# Power.net
KiCad netlist of a schematic drawn in Altium Designer
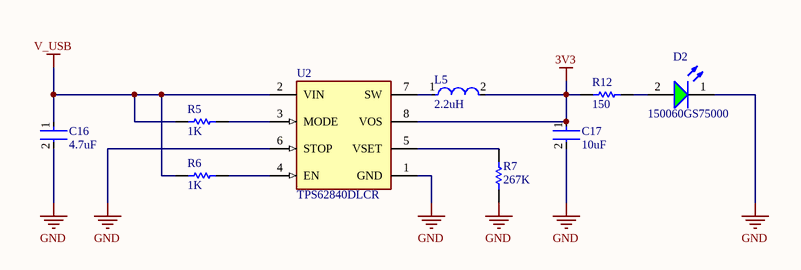
[diagram p0: Power.SchDoc]

(export (version "E")
  (design (tool "Eeschema 10.0.6"))
  (components
    (comp (ref "C16")
      (value "4.7uF")
      (footprint "FP-CC0402-MFG")
      (description "CAP CER 4.7UF 16V X5R 0402")
      (fields
        (field (name "OCTOPART") "https://octopart.com/cc0402mrx5r7bb475-yageo-81932628")
        (field (name "MANUFACTURER PART NUMBER") "CC0402MRX5R7BB475")
      )
      (libsource (lib "Altium Content Vault") (part "11868f565c42a9108669ba33697ecf6"))
    )
    (comp (ref "C17")
      (value "10uF")
      (footprint "FP-CL07-IPC_C")
      (description "Cap Ceramic 10uF 10V X5R ±20% SMD 0402 +85°C Paper T/R")
      (fields (field (name "TOLERANCE") "20%"))
      (libsource (lib "Altium Content Vault") (part "b4654b650e69147ec39a6b967a45e02"))
    )
    (comp (ref "D2")
      (value "150060GS75000")
      (footprint "WL-SMCW_0603_150060xx75000")
      (description "430mcd Colorless transparence 520nm Emerald 140° LED0603 Light Emitting Diodes (LED) ROHS")
      (libsource (lib "Altium Content Vault") (part "LED_Green_2A-1K"))
    )
    (comp (ref "L5")
      (value "2.2uH")
      (footprint "FP-MLZ1005-IPC_B")
      (description "Shielded Multilayer Inductor 2.2uH ±20% 350mA 715mΩ SMD 0402")
      (fields (field (name "TOLERANCE") "20%"))
      (libsource (lib "Altium Content Vault") (part "725321dda6339637d4d059423bc1c3c"))
    )
    (comp (ref "R5")
      (value "1K")
      (footprint "RESC0603X28X15ML05T05")
      (fields (field (name "MANUFACTURER") "Vishay Dale") (field (name "PART NUMBER") "CRCW02011K00FNED"))
      (libsource (lib "Altium Content Vault") (part "RES"))
    )
    (comp (ref "R6")
      (value "1K")
      (footprint "RESC0603X28X15ML05T05")
      (fields (field (name "MANUFACTURER") "Vishay Dale") (field (name "PART NUMBER") "CRCW02011K00FNED"))
      (libsource (lib "Altium Content Vault") (part "RES"))
    )
    (comp (ref "R7")
      (value "267K")
      (footprint "RESC1005X40X25ML05T05")
      (fields (field (name "PART NUMBER") "ERJ-2RKF2673X") (field (name "MANUFACTURER") "Panasonic"))
      (libsource (lib "Altium Content Vault") (part "RES"))
    )
    (comp (ref "R12")
      (value "150")
      (footprint "RESC0603X26X15ML03T05")
      (fields (field (name "MANUFACTURER") "Panasonic") (field (name "PART NUMBER") "ERJ1GNF1500C"))
      (libsource (lib "Altium Content Vault") (part "RES"))
    )
    (comp (ref "U2")
      (value "TPS62840DLCR")
      (footprint "FP-DLC0008B-MFG")
      (description "ULTRA LOW IQ BUCK CONVERTER")
      (fields
        (field (name "OCTOPART") "https://octopart.com/tps62840dlcr-texas+instruments-103121111")
        (field (name "MANUFACTURER") "Texas Instruments")
      )
      (libsource (lib "Altium Content Vault") (part "09bc3a9b1d58a1376198d6b923e8c7c"))
    )
  )
  (nets
    (net (code "1") (name "3V3") (class "Default")
      (node (ref "C17") (pin "1") (pinfunction "1_1") (pintype "passive"))
      (node (ref "L5") (pin "2") (pinfunction "2_2") (pintype "passive"))
      (node (ref "R12") (pin "1") (pinfunction "1_1") (pintype "passive"))
      (node (ref "U2") (pin "8") (pinfunction "VOS_8") (pintype "passive"))
    )
    (net (code "2") (name "GND") (class "Default")
      (node (ref "C16") (pin "2") (pinfunction "2_2") (pintype "passive"))
      (node (ref "C17") (pin "2") (pinfunction "2_2") (pintype "passive"))
      (node (ref "D2") (pin "1") (pinfunction "K_1") (pintype "passive"))
      (node (ref "R7") (pin "1") (pinfunction "1_1") (pintype "passive"))
      (node (ref "U2") (pin "1") (pinfunction "GND_1") (pintype "power_in"))
      (node (ref "U2") (pin "6") (pinfunction "STOP_6") (pintype "input"))
    )
    (net (code "3") (name "Net-(D2-A)") (class "Default")
      (node (ref "D2") (pin "2") (pinfunction "A_2") (pintype "passive"))
      (node (ref "R12") (pin "2") (pinfunction "2_2") (pintype "passive"))
    )
    (net (code "4") (name "Net-(U2-EN)") (class "Default")
      (node (ref "R6") (pin "2") (pinfunction "2_2") (pintype "passive"))
      (node (ref "U2") (pin "4") (pinfunction "EN_4") (pintype "input"))
    )
    (net (code "5") (name "Net-(U2-MODE)") (class "Default")
      (node (ref "R5") (pin "2") (pinfunction "2_2") (pintype "passive"))
      (node (ref "U2") (pin "3") (pinfunction "MODE_3") (pintype "input"))
    )
    (net (code "6") (name "Net-(U2-SW)") (class "Default")
      (node (ref "L5") (pin "1") (pinfunction "1_1") (pintype "passive"))
      (node (ref "U2") (pin "7") (pinfunction "SW_7") (pintype "passive"))
    )
    (net (code "7") (name "Net-(U2-VSET)") (class "Default")
      (node (ref "R7") (pin "2") (pinfunction "2_2") (pintype "passive"))
      (node (ref "U2") (pin "5") (pinfunction "VSET_5") (pintype "passive"))
    )
    (net (code "8") (name "V_USB") (class "Default")
      (node (ref "C16") (pin "1") (pinfunction "1_1") (pintype "passive"))
      (node (ref "R5") (pin "1") (pinfunction "1_1") (pintype "passive"))
      (node (ref "R6") (pin "1") (pinfunction "1_1") (pintype "passive"))
      (node (ref "U2") (pin "2") (pinfunction "VIN_2") (pintype "power_in"))
    )
  )
)
